# conect_sheet.net
KiCad netlist of a schematic drawn in Altium Designer
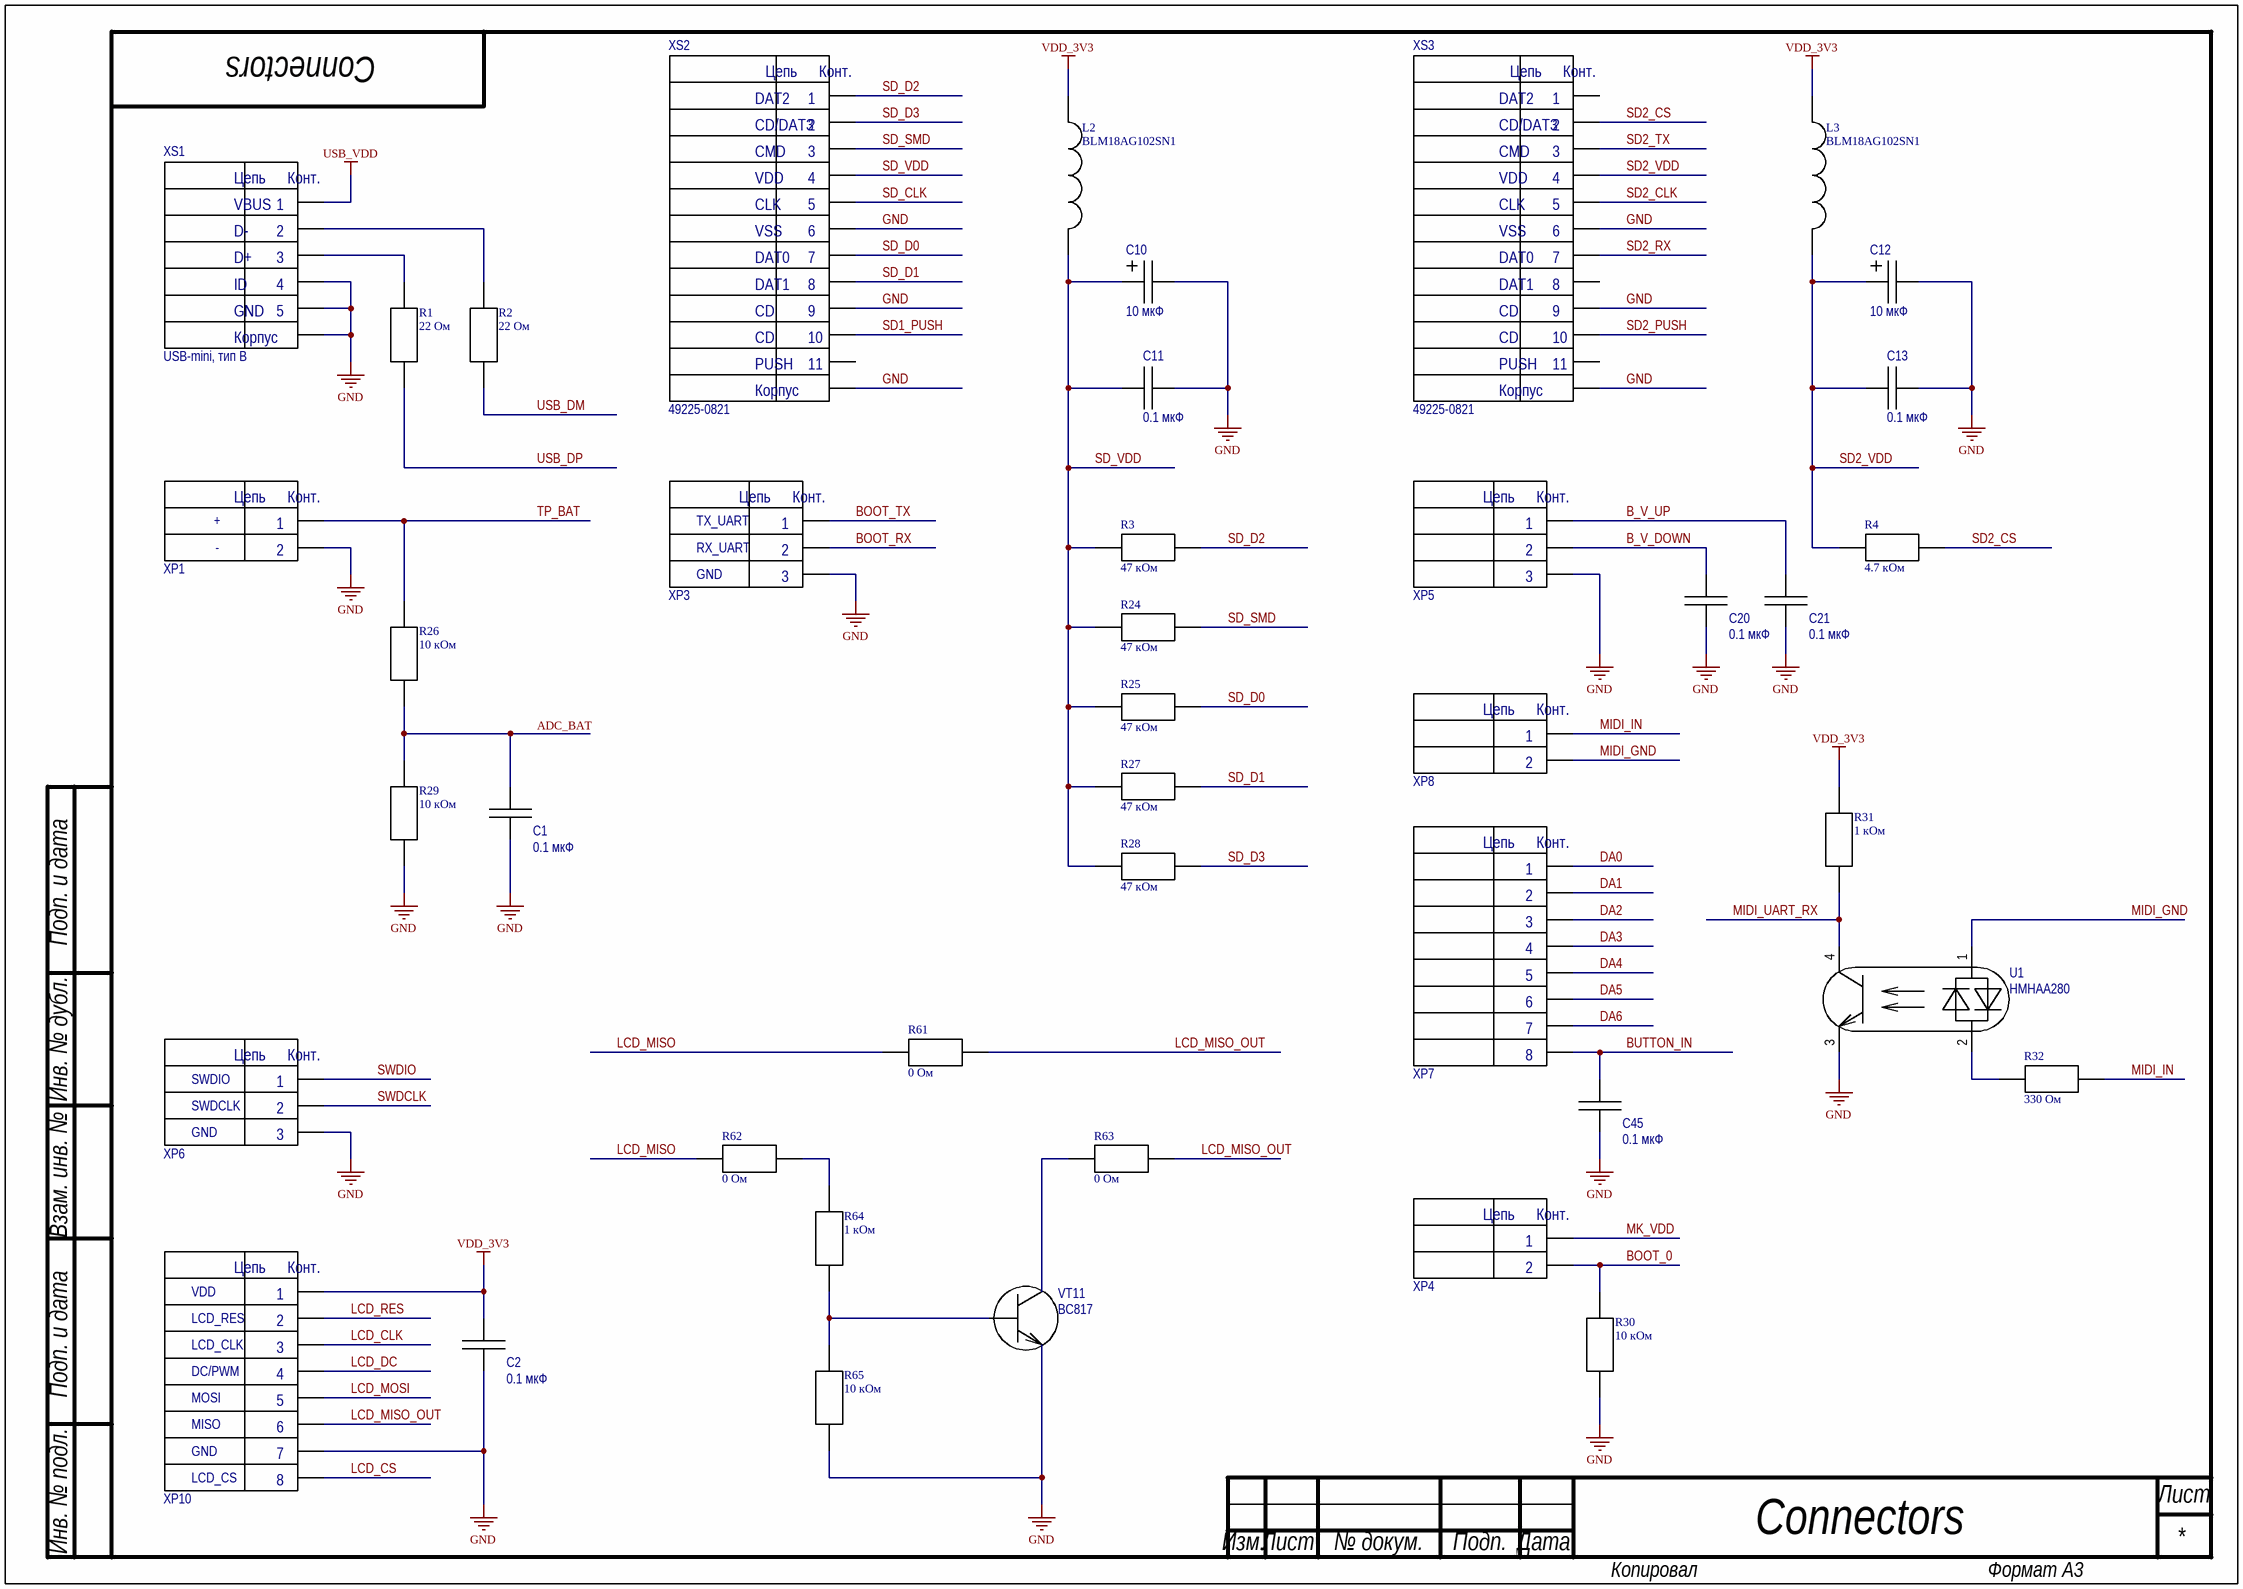
[diagram p0: conect_sheet.SchDoc]

(export (version "E")
  (design (tool "Eeschema 10.0.6"))
  (components
    (comp (ref "C1")
      (value "0.1 мкФ")
      (footprint "C 1206")
      (description "SMD Capacitor 1206")
      (fields
        (field (name "TOLERANCE") "/Укажите допуск в процентах/")
        (field (name "MANUFACTURER") "/Укажите компанию-производителя/")
      )
      (libsource (lib "my_lib") (part "CAP 1206"))
    )
    (comp (ref "C2")
      (value "0.1 мкФ")
      (footprint "C 1206")
      (description "SMD Capacitor 1206")
      (fields
        (field (name "TOLERANCE") "/Укажите допуск в процентах/")
        (field (name "MANUFACTURER") "/Укажите компанию-производителя/")
      )
      (libsource (lib "my_lib") (part "CAP 1206"))
    )
    (comp (ref "C10")
      (value "10 мкФ")
      (footprint "C TAN_C")
      (description "SMD Tantalium Capacitor C")
      (fields
        (field (name "TOLERANCE") "/Укажите допуск в процентах/")
        (field (name "MANUFACTURER") "/Укажите компанию-производителя/")
      )
      (libsource (lib "my_lib") (part "CAP TAN_C"))
    )
    (comp (ref "C11")
      (value "0.1 мкФ")
      (footprint "C 1206")
      (description "SMD Capacitor 1206")
      (fields
        (field (name "TOLERANCE") "/Укажите допуск в процентах/")
        (field (name "MANUFACTURER") "/Укажите компанию-производителя/")
      )
      (libsource (lib "my_lib") (part "CAP 1206"))
    )
    (comp (ref "C12")
      (value "10 мкФ")
      (footprint "C TAN_C")
      (description "SMD Tantalium Capacitor C")
      (fields
        (field (name "TOLERANCE") "/Укажите допуск в процентах/")
        (field (name "MANUFACTURER") "/Укажите компанию-производителя/")
      )
      (libsource (lib "my_lib") (part "CAP TAN_C"))
    )
    (comp (ref "C13")
      (value "0.1 мкФ")
      (footprint "C 1206")
      (description "SMD Capacitor 1206")
      (fields
        (field (name "TOLERANCE") "/Укажите допуск в процентах/")
        (field (name "MANUFACTURER") "/Укажите компанию-производителя/")
      )
      (libsource (lib "my_lib") (part "CAP 1206"))
    )
    (comp (ref "C20")
      (value "0.1 мкФ")
      (footprint "C 1206")
      (description "SMD Capacitor 1206")
      (fields
        (field (name "TOLERANCE") "/Укажите допуск в процентах/")
        (field (name "MANUFACTURER") "/Укажите компанию-производителя/")
      )
      (libsource (lib "my_lib") (part "CAP 1206"))
    )
    (comp (ref "C21")
      (value "0.1 мкФ")
      (footprint "C 1206")
      (description "SMD Capacitor 1206")
      (fields
        (field (name "TOLERANCE") "/Укажите допуск в процентах/")
        (field (name "MANUFACTURER") "/Укажите компанию-производителя/")
      )
      (libsource (lib "my_lib") (part "CAP 1206"))
    )
    (comp (ref "C45")
      (value "0.1 мкФ")
      (footprint "C 1206")
      (description "SMD Capacitor 1206")
      (fields
        (field (name "TOLERANCE") "/Укажите допуск в процентах/")
        (field (name "MANUFACTURER") "/Укажите компанию-производителя/")
      )
      (libsource (lib "my_lib") (part "CAP 1206"))
    )
    (comp (ref "L2")
      (value "BLM18AG102SN1")
      (footprint "FB 0603")
      (libsource (lib "my_lib") (part "BLM18AG102SN1"))
    )
    (comp (ref "L3")
      (value "BLM18AG102SN1")
      (footprint "FB 0603")
      (libsource (lib "my_lib") (part "BLM18AG102SN1"))
    )
    (comp (ref "R1") (value "22 Ом") (footprint "RES 0805") (libsource (lib "my_lib") (part "RES 0805")))
    (comp (ref "R2") (value "22 Ом") (footprint "RES 0805") (libsource (lib "my_lib") (part "RES 0805")))
    (comp (ref "R3") (value "47 кОм") (footprint "RES 0805") (libsource (lib "my_lib") (part "RES 0805")))
    (comp (ref "R4") (value "4.7 кОм") (footprint "RES 0805") (libsource (lib "my_lib") (part "RES 0805")))
    (comp (ref "R24") (value "47 кОм") (footprint "RES 0805") (libsource (lib "my_lib") (part "RES 0805")))
    (comp (ref "R25") (value "47 кОм") (footprint "RES 0805") (libsource (lib "my_lib") (part "RES 0805")))
    (comp (ref "R26") (value "10 кОм") (footprint "RES 0805") (libsource (lib "my_lib") (part "RES 0805")))
    (comp (ref "R27") (value "47 кОм") (footprint "RES 0805") (libsource (lib "my_lib") (part "RES 0805")))
    (comp (ref "R28") (value "47 кОм") (footprint "RES 0805") (libsource (lib "my_lib") (part "RES 0805")))
    (comp (ref "R29") (value "10 кОм") (footprint "RES 0805") (libsource (lib "my_lib") (part "RES 0805")))
    (comp (ref "R30") (value "10 кОм") (footprint "RES 0805") (libsource (lib "my_lib") (part "RES 0805")))
    (comp (ref "R31") (value "1 кОм") (footprint "RES 0805") (libsource (lib "my_lib") (part "RES 0805")))
    (comp (ref "R32") (value "330 Ом") (footprint "RES 0805") (libsource (lib "my_lib") (part "RES 0805")))
    (comp (ref "R61") (value "0 Ом") (footprint "RES 0805") (libsource (lib "my_lib") (part "RES 0805")))
    (comp (ref "R62") (value "0 Ом") (footprint "RES 0805") (libsource (lib "my_lib") (part "RES 0805")))
    (comp (ref "R63") (value "0 Ом") (footprint "RES 0805") (libsource (lib "my_lib") (part "RES 0805")))
    (comp (ref "R64") (value "1 кОм") (footprint "RES 0805") (libsource (lib "my_lib") (part "RES 0805")))
    (comp (ref "R65") (value "10 кОм") (footprint "RES 0805") (libsource (lib "my_lib") (part "RES 0805")))
    (comp (ref "U1")
      (value "HMHAA280")
      (footprint "MFP-4L")
      (description "AC Input Half Pitch Mini-Flat Package 4-pin Optocoupler")
      (fields (field (name "MANUFACTURER") "Fairchild Semiconductor"))
      (libsource (lib "my_lib") (part "HMHAA280"))
    )
    (comp (ref "VT11")
      (value "BC817")
      (footprint "SOT-23")
      (description "NPN general-purpose transistor")
      (fields (field (name "MANUFACTURER") "NXP"))
      (libsource (lib "my_lib") (part "BC817"))
    )
    (comp (ref "XP1")
      (value "PLS-2")
      (footprint "PLS-2")
      (description "PLS connector")
      (fields (field (name "MANUFACTURER") "NONAME"))
      (libsource (lib "my_lib") (part "PLS-2"))
    )
    (comp (ref "XP3")
      (value "PLS-3")
      (footprint "PLS-3")
      (description "PLS connector")
      (fields (field (name "MANUFACTURER") "NONAME"))
      (libsource (lib "my_lib") (part "PLS-3"))
    )
    (comp (ref "XP4")
      (value "PLS-2")
      (footprint "PLS-2")
      (description "PLS connector")
      (fields (field (name "MANUFACTURER") "NONAME"))
      (libsource (lib "my_lib") (part "PLS-2"))
    )
    (comp (ref "XP5")
      (value "PLS-3")
      (footprint "PLS-3")
      (description "PLS connector")
      (fields (field (name "MANUFACTURER") "NONAME"))
      (libsource (lib "my_lib") (part "PLS-3"))
    )
    (comp (ref "XP6")
      (value "PLS-3")
      (footprint "PLS-3")
      (description "PLS connector")
      (fields (field (name "MANUFACTURER") "NONAME"))
      (libsource (lib "my_lib") (part "PLS-3"))
    )
    (comp (ref "XP7")
      (value "PLD-8")
      (footprint "PLD-8")
      (description "PLD connector")
      (fields (field (name "MANUFACTURER") "NONAME"))
      (libsource (lib "my_lib") (part "PLD-8"))
    )
    (comp (ref "XP8")
      (value "PLS-2")
      (footprint "PLS-2")
      (description "PLS connector")
      (fields (field (name "MANUFACTURER") "NONAME"))
      (libsource (lib "my_lib") (part "PLS-2"))
    )
    (comp (ref "XP10")
      (value "PLD-8")
      (footprint "PLD-8")
      (description "PLD connector")
      (fields (field (name "MANUFACTURER") "NONAME"))
      (libsource (lib "my_lib") (part "PLD-8"))
    )
    (comp (ref "XS1")
      (value "USB-mini, тип B")
      (footprint "USB_mini_B")
      (description "USB-mini-B connector")
      (fields (field (name "MANUFACTURER") "NONAME"))
      (libsource (lib "my_lib") (part "USB-mini_B"))
    )
    (comp (ref "XS2")
      (value "49225-0821")
      (footprint "MOLEX 49225-0821")
      (description "MOLEX MicroSD connector")
      (fields (field (name "MANUFACTURER") "Molex"))
      (libsource (lib "my_lib") (part "49225-0821"))
    )
    (comp (ref "XS3")
      (value "49225-0821")
      (footprint "MOLEX 49225-0821")
      (description "MOLEX MicroSD connector")
      (fields (field (name "MANUFACTURER") "Molex"))
      (libsource (lib "my_lib") (part "49225-0821"))
    )
  )
  (nets
    (net (code "1") (name "/ADC_BAT") (class "Default")
      (node (ref "C1") (pin "1") (pinfunction "1_1") (pintype "passive"))
      (node (ref "R26") (pin "1") (pinfunction "1_1") (pintype "passive"))
      (node (ref "R29") (pin "2") (pinfunction "2_2") (pintype "passive"))
    )
    (net (code "2") (name "/BOOT_0") (class "Default")
      (node (ref "R30") (pin "2") (pinfunction "2_2") (pintype "passive"))
      (node (ref "XP4") (pin "2") (pinfunction "2_2") (pintype "passive"))
    )
    (net (code "3") (name "/BOOT_RX") (class "Default")
      (node (ref "XP3") (pin "2") (pinfunction "2_2") (pintype "passive"))
    )
    (net (code "4") (name "/BOOT_TX") (class "Default")
      (node (ref "XP3") (pin "1") (pinfunction "1_1") (pintype "passive"))
    )
    (net (code "5") (name "/BUTTON_IN") (class "Default")
      (node (ref "C45") (pin "1") (pinfunction "1_1") (pintype "passive"))
      (node (ref "XP7") (pin "8") (pinfunction "8_8") (pintype "passive"))
    )
    (net (code "6") (name "/B_V_DOWN") (class "Default")
      (node (ref "C20") (pin "1") (pinfunction "1_1") (pintype "passive"))
      (node (ref "XP5") (pin "2") (pinfunction "2_2") (pintype "passive"))
    )
    (net (code "7") (name "/B_V_UP") (class "Default")
      (node (ref "C21") (pin "1") (pinfunction "1_1") (pintype "passive"))
      (node (ref "XP5") (pin "1") (pinfunction "1_1") (pintype "passive"))
    )
    (net (code "8") (name "/DA0") (class "Default")
      (node (ref "XP7") (pin "1") (pinfunction "1_1") (pintype "passive"))
    )
    (net (code "9") (name "/DA1") (class "Default")
      (node (ref "XP7") (pin "2") (pinfunction "2_2") (pintype "passive"))
    )
    (net (code "10") (name "/DA2") (class "Default")
      (node (ref "XP7") (pin "3") (pinfunction "3_3") (pintype "passive"))
    )
    (net (code "11") (name "/DA3") (class "Default")
      (node (ref "XP7") (pin "4") (pinfunction "4_4") (pintype "passive"))
    )
    (net (code "12") (name "/DA4") (class "Default")
      (node (ref "XP7") (pin "5") (pinfunction "5_5") (pintype "passive"))
    )
    (net (code "13") (name "/DA5") (class "Default")
      (node (ref "XP7") (pin "6") (pinfunction "6_6") (pintype "passive"))
    )
    (net (code "14") (name "/DA6") (class "Default")
      (node (ref "XP7") (pin "7") (pinfunction "7_7") (pintype "passive"))
    )
    (net (code "15") (name "/LCD_CLK") (class "Default")
      (node (ref "XP10") (pin "3") (pinfunction "3_3") (pintype "passive"))
    )
    (net (code "16") (name "/LCD_CS") (class "Default")
      (node (ref "XP10") (pin "8") (pinfunction "8_8") (pintype "passive"))
    )
    (net (code "17") (name "/LCD_DC") (class "Default")
      (node (ref "XP10") (pin "4") (pinfunction "4_4") (pintype "passive"))
    )
    (net (code "18") (name "/LCD_MISO") (class "Default")
      (node (ref "R61") (pin "1") (pinfunction "1_1") (pintype "passive"))
      (node (ref "R62") (pin "2") (pinfunction "2_2") (pintype "passive"))
    )
    (net (code "19") (name "/LCD_MISO_OUT") (class "Default")
      (node (ref "R61") (pin "2") (pinfunction "2_2") (pintype "passive"))
      (node (ref "R63") (pin "1") (pinfunction "1_1") (pintype "passive"))
      (node (ref "XP10") (pin "6") (pinfunction "6_6") (pintype "passive"))
    )
    (net (code "20") (name "/LCD_MOSI") (class "Default")
      (node (ref "XP10") (pin "5") (pinfunction "5_5") (pintype "passive"))
    )
    (net (code "21") (name "/LCD_RES") (class "Default")
      (node (ref "XP10") (pin "2") (pinfunction "2_2") (pintype "passive"))
    )
    (net (code "22") (name "/MIDI_GND") (class "Default")
      (node (ref "U1") (pin "1") (pinfunction "AC_1") (pintype "passive"))
      (node (ref "XP8") (pin "2") (pinfunction "2_2") (pintype "passive"))
    )
    (net (code "23") (name "/MIDI_IN") (class "Default")
      (node (ref "R32") (pin "2") (pinfunction "2_2") (pintype "passive"))
      (node (ref "XP8") (pin "1") (pinfunction "1_1") (pintype "passive"))
    )
    (net (code "24") (name "/MIDI_UART_RX") (class "Default")
      (node (ref "R31") (pin "1") (pinfunction "1_1") (pintype "passive"))
      (node (ref "U1") (pin "4") (pinfunction "C_4") (pintype "passive"))
    )
    (net (code "25") (name "/MK_VDD") (class "Default")
      (node (ref "XP4") (pin "1") (pinfunction "1_1") (pintype "passive"))
    )
    (net (code "26") (name "/SD1_PUSH") (class "Default")
      (node (ref "XS2") (pin "10") (pinfunction "10_10") (pintype "passive"))
    )
    (net (code "27") (name "/SD2_CLK") (class "Default")
      (node (ref "XS3") (pin "5") (pinfunction "5_5") (pintype "passive"))
    )
    (net (code "28") (name "/SD2_CS") (class "Default")
      (node (ref "R4") (pin "2") (pinfunction "2_2") (pintype "passive"))
      (node (ref "XS3") (pin "2") (pinfunction "2_2") (pintype "passive"))
    )
    (net (code "29") (name "/SD2_PUSH") (class "Default")
      (node (ref "XS3") (pin "10") (pinfunction "10_10") (pintype "passive"))
    )
    (net (code "30") (name "/SD2_RX") (class "Default")
      (node (ref "XS3") (pin "7") (pinfunction "7_7") (pintype "passive"))
    )
    (net (code "31") (name "/SD2_TX") (class "Default")
      (node (ref "XS3") (pin "3") (pinfunction "3_3") (pintype "passive"))
    )
    (net (code "32") (name "/SD2_VDD") (class "Default")
      (node (ref "C12") (pin "1") (pinfunction "1_1") (pintype "passive"))
      (node (ref "C13") (pin "1") (pinfunction "1_1") (pintype "passive"))
      (node (ref "L3") (pin "2") (pinfunction "2_2") (pintype "passive"))
      (node (ref "R4") (pin "1") (pinfunction "1_1") (pintype "passive"))
      (node (ref "XS3") (pin "4") (pinfunction "4_4") (pintype "passive"))
    )
    (net (code "33") (name "/SD_CLK") (class "Default")
      (node (ref "XS2") (pin "5") (pinfunction "5_5") (pintype "passive"))
    )
    (net (code "34") (name "/SD_D0") (class "Default")
      (node (ref "R25") (pin "2") (pinfunction "2_2") (pintype "passive"))
      (node (ref "XS2") (pin "7") (pinfunction "7_7") (pintype "passive"))
    )
    (net (code "35") (name "/SD_D1") (class "Default")
      (node (ref "R27") (pin "2") (pinfunction "2_2") (pintype "passive"))
      (node (ref "XS2") (pin "8") (pinfunction "8_8") (pintype "passive"))
    )
    (net (code "36") (name "/SD_D2") (class "Default")
      (node (ref "R3") (pin "2") (pinfunction "2_2") (pintype "passive"))
      (node (ref "XS2") (pin "1") (pinfunction "1_1") (pintype "passive"))
    )
    (net (code "37") (name "/SD_D3") (class "Default")
      (node (ref "R28") (pin "2") (pinfunction "2_2") (pintype "passive"))
      (node (ref "XS2") (pin "2") (pinfunction "2_2") (pintype "passive"))
    )
    (net (code "38") (name "/SD_SMD") (class "Default")
      (node (ref "R24") (pin "2") (pinfunction "2_2") (pintype "passive"))
      (node (ref "XS2") (pin "3") (pinfunction "3_3") (pintype "passive"))
    )
    (net (code "39") (name "/SD_VDD") (class "Default")
      (node (ref "C10") (pin "1") (pinfunction "1_1") (pintype "passive"))
      (node (ref "C11") (pin "1") (pinfunction "1_1") (pintype "passive"))
      (node (ref "L2") (pin "2") (pinfunction "2_2") (pintype "passive"))
      (node (ref "R24") (pin "1") (pinfunction "1_1") (pintype "passive"))
      (node (ref "R25") (pin "1") (pinfunction "1_1") (pintype "passive"))
      (node (ref "R27") (pin "1") (pinfunction "1_1") (pintype "passive"))
      (node (ref "R28") (pin "1") (pinfunction "1_1") (pintype "passive"))
      (node (ref "R3") (pin "1") (pinfunction "1_1") (pintype "passive"))
      (node (ref "XS2") (pin "4") (pinfunction "4_4") (pintype "passive"))
    )
    (net (code "40") (name "/SWDCLK") (class "Default")
      (node (ref "XP6") (pin "2") (pinfunction "2_2") (pintype "passive"))
    )
    (net (code "41") (name "/SWDIO") (class "Default")
      (node (ref "XP6") (pin "1") (pinfunction "1_1") (pintype "passive"))
    )
    (net (code "42") (name "/TP_BAT") (class "Default")
      (node (ref "R26") (pin "2") (pinfunction "2_2") (pintype "passive"))
      (node (ref "XP1") (pin "1") (pinfunction "1_1") (pintype "passive"))
    )
    (net (code "43") (name "/USB_DM") (class "Default")
      (node (ref "R2") (pin "1") (pinfunction "1_1") (pintype "passive"))
    )
    (net (code "44") (name "/USB_DP") (class "Default")
      (node (ref "R1") (pin "1") (pinfunction "1_1") (pintype "passive"))
    )
    (net (code "45") (name "GND") (class "Default")
      (node (ref "C1") (pin "2") (pinfunction "2_2") (pintype "passive"))
      (node (ref "C10") (pin "2") (pinfunction "2_2") (pintype "passive"))
      (node (ref "C11") (pin "2") (pinfunction "2_2") (pintype "passive"))
      (node (ref "C12") (pin "2") (pinfunction "2_2") (pintype "passive"))
      (node (ref "C13") (pin "2") (pinfunction "2_2") (pintype "passive"))
      (node (ref "C2") (pin "2") (pinfunction "2_2") (pintype "passive"))
      (node (ref "C20") (pin "2") (pinfunction "2_2") (pintype "passive"))
      (node (ref "C21") (pin "2") (pinfunction "2_2") (pintype "passive"))
      (node (ref "C45") (pin "2") (pinfunction "2_2") (pintype "passive"))
      (node (ref "R29") (pin "1") (pinfunction "1_1") (pintype "passive"))
      (node (ref "R30") (pin "1") (pinfunction "1_1") (pintype "passive"))
      (node (ref "R65") (pin "1") (pinfunction "1_1") (pintype "passive"))
      (node (ref "U1") (pin "3") (pinfunction "E_3") (pintype "passive"))
      (node (ref "VT11") (pin "2") (pinfunction "E_2") (pintype "passive"))
      (node (ref "XP1") (pin "2") (pinfunction "2_2") (pintype "passive"))
      (node (ref "XP10") (pin "7") (pinfunction "7_7") (pintype "passive"))
      (node (ref "XP3") (pin "3") (pinfunction "3_3") (pintype "passive"))
      (node (ref "XP5") (pin "3") (pinfunction "3_3") (pintype "passive"))
      (node (ref "XP6") (pin "3") (pinfunction "3_3") (pintype "passive"))
      (node (ref "XS1") (pin "0") (pinfunction "0_0") (pintype "passive"))
      (node (ref "XS1") (pin "4") (pinfunction "CASE_4") (pintype "passive"))
      (node (ref "XS1") (pin "5") (pinfunction "GND_5") (pintype "passive"))
      (node (ref "XS2") (pin "0") (pinfunction "0_0") (pintype "passive"))
      (node (ref "XS2") (pin "6") (pinfunction "6_6") (pintype "passive"))
      (node (ref "XS2") (pin "9") (pinfunction "9_9") (pintype "passive"))
      (node (ref "XS3") (pin "0") (pinfunction "0_0") (pintype "passive"))
      (node (ref "XS3") (pin "6") (pinfunction "6_6") (pintype "passive"))
      (node (ref "XS3") (pin "9") (pinfunction "9_9") (pintype "passive"))
    )
    (net (code "46") (name "Net-(R62-Pad1)") (class "Default")
      (node (ref "R62") (pin "1") (pinfunction "1_1") (pintype "passive"))
      (node (ref "R64") (pin "2") (pinfunction "2_2") (pintype "passive"))
    )
    (net (code "47") (name "Net-(U1-CA)") (class "Default")
      (node (ref "R32") (pin "1") (pinfunction "1_1") (pintype "passive"))
      (node (ref "U1") (pin "2") (pinfunction "CA_2") (pintype "passive"))
    )
    (net (code "48") (name "Net-(VT11-B)") (class "Default")
      (node (ref "R64") (pin "1") (pinfunction "1_1") (pintype "passive"))
      (node (ref "R65") (pin "2") (pinfunction "2_2") (pintype "passive"))
      (node (ref "VT11") (pin "1") (pinfunction "B_1") (pintype "passive"))
    )
    (net (code "49") (name "Net-(VT11-C)") (class "Default")
      (node (ref "R63") (pin "2") (pinfunction "2_2") (pintype "passive"))
      (node (ref "VT11") (pin "3") (pinfunction "C_3") (pintype "passive"))
    )
    (net (code "50") (name "Net-(XS1-D+)") (class "Default")
      (node (ref "R1") (pin "2") (pinfunction "2_2") (pintype "passive"))
      (node (ref "XS1") (pin "3") (pinfunction "D+_3") (pintype "passive"))
    )
    (net (code "51") (name "Net-(XS1-D-)") (class "Default")
      (node (ref "R2") (pin "2") (pinfunction "2_2") (pintype "passive"))
      (node (ref "XS1") (pin "2") (pinfunction "D-_2") (pintype "passive"))
    )
    (net (code "52") (name "USB_VDD") (class "Default")
      (node (ref "XS1") (pin "1") (pinfunction "VBUS_1") (pintype "passive"))
    )
    (net (code "53") (name "VDD_3V3") (class "Default")
      (node (ref "C2") (pin "1") (pinfunction "1_1") (pintype "passive"))
      (node (ref "L2") (pin "1") (pinfunction "1_1") (pintype "passive"))
      (node (ref "L3") (pin "1") (pinfunction "1_1") (pintype "passive"))
      (node (ref "R31") (pin "2") (pinfunction "2_2") (pintype "passive"))
      (node (ref "XP10") (pin "1") (pinfunction "1_1") (pintype "passive"))
    )
    (net (code "54") (name "unconnected-(XS2-Pad11)") (class "Default")
      (node (ref "XS2") (pin "11") (pinfunction "11_11") (pintype "passive"))
    )
    (net (code "55") (name "unconnected-(XS3-Pad1)") (class "Default")
      (node (ref "XS3") (pin "1") (pinfunction "1_1") (pintype "passive"))
    )
    (net (code "56") (name "unconnected-(XS3-Pad8)") (class "Default")
      (node (ref "XS3") (pin "8") (pinfunction "8_8") (pintype "passive"))
    )
    (net (code "57") (name "unconnected-(XS3-Pad11)") (class "Default")
      (node (ref "XS3") (pin "11") (pinfunction "11_11") (pintype "passive"))
    )
  )
)
